# LED_low_side_connector.net
KiCad netlist of a schematic drawn in Altium Designer
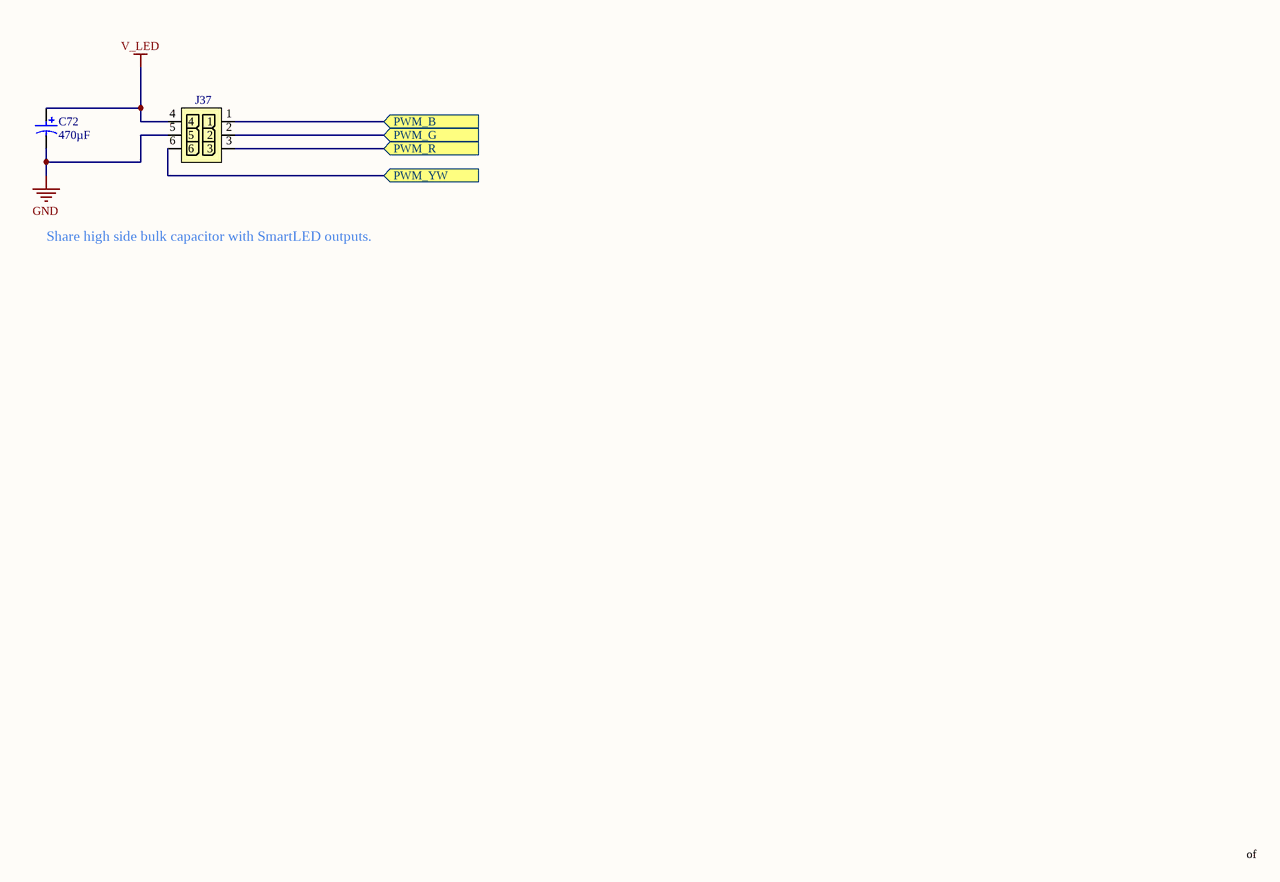
[diagram p0: LED_low_side_connector.SchDoc]

(export (version "E")
  (design (tool "Eeschema 10.0.6"))
  (components
    (comp (ref "C72")
      (value "470µF")
      (footprint "CAP_POL_DIAM10_H22_SPACING5")
      (description "CAP ALUM 470UF 20% 50V RADIAL TH")
      (fields (field (name "TOLERANCE") "20%") (field (name "Comment") "REH1020471M050K"))
      (libsource (lib "Equus Computer Systems") (part "CAP-P-2"))
    )
    (comp (ref "J37")
      (value "212528-0600")
      (footprint "212528-0600-Footprint-1")
      (description "Connector, Micro-Fit+ Right Angle 6ckt Header - Tin")
      (libsource (lib "Equus Computer Systems") (part "212528-0600-Symbol-1"))
    )
  )
  (nets
    (net (code "1") (name "/PWM_B") (class "Default")
      (node (ref "J37") (pin "1") (pinfunction "1_1") (pintype "passive"))
    )
    (net (code "2") (name "/PWM_G") (class "Default")
      (node (ref "J37") (pin "2") (pinfunction "2_2") (pintype "passive"))
    )
    (net (code "3") (name "/PWM_R") (class "Default")
      (node (ref "J37") (pin "3") (pinfunction "3_3") (pintype "passive"))
    )
    (net (code "4") (name "/PWM_YW") (class "Default")
      (node (ref "J37") (pin "6") (pinfunction "6_6") (pintype "passive"))
    )
    (net (code "5") (name "GND") (class "Default")
      (node (ref "C72") (pin "2") (pinfunction "2_2") (pintype "passive"))
      (node (ref "J37") (pin "5") (pinfunction "5_5") (pintype "passive"))
    )
    (net (code "6") (name "V_LED") (class "Default")
      (node (ref "C72") (pin "1") (pinfunction "1_1") (pintype "passive"))
      (node (ref "J37") (pin "4") (pinfunction "4_4") (pintype "passive"))
    )
  )
)
